# MI0283QT_v11.net
KiCad netlist of a schematic drawn in EAGLE
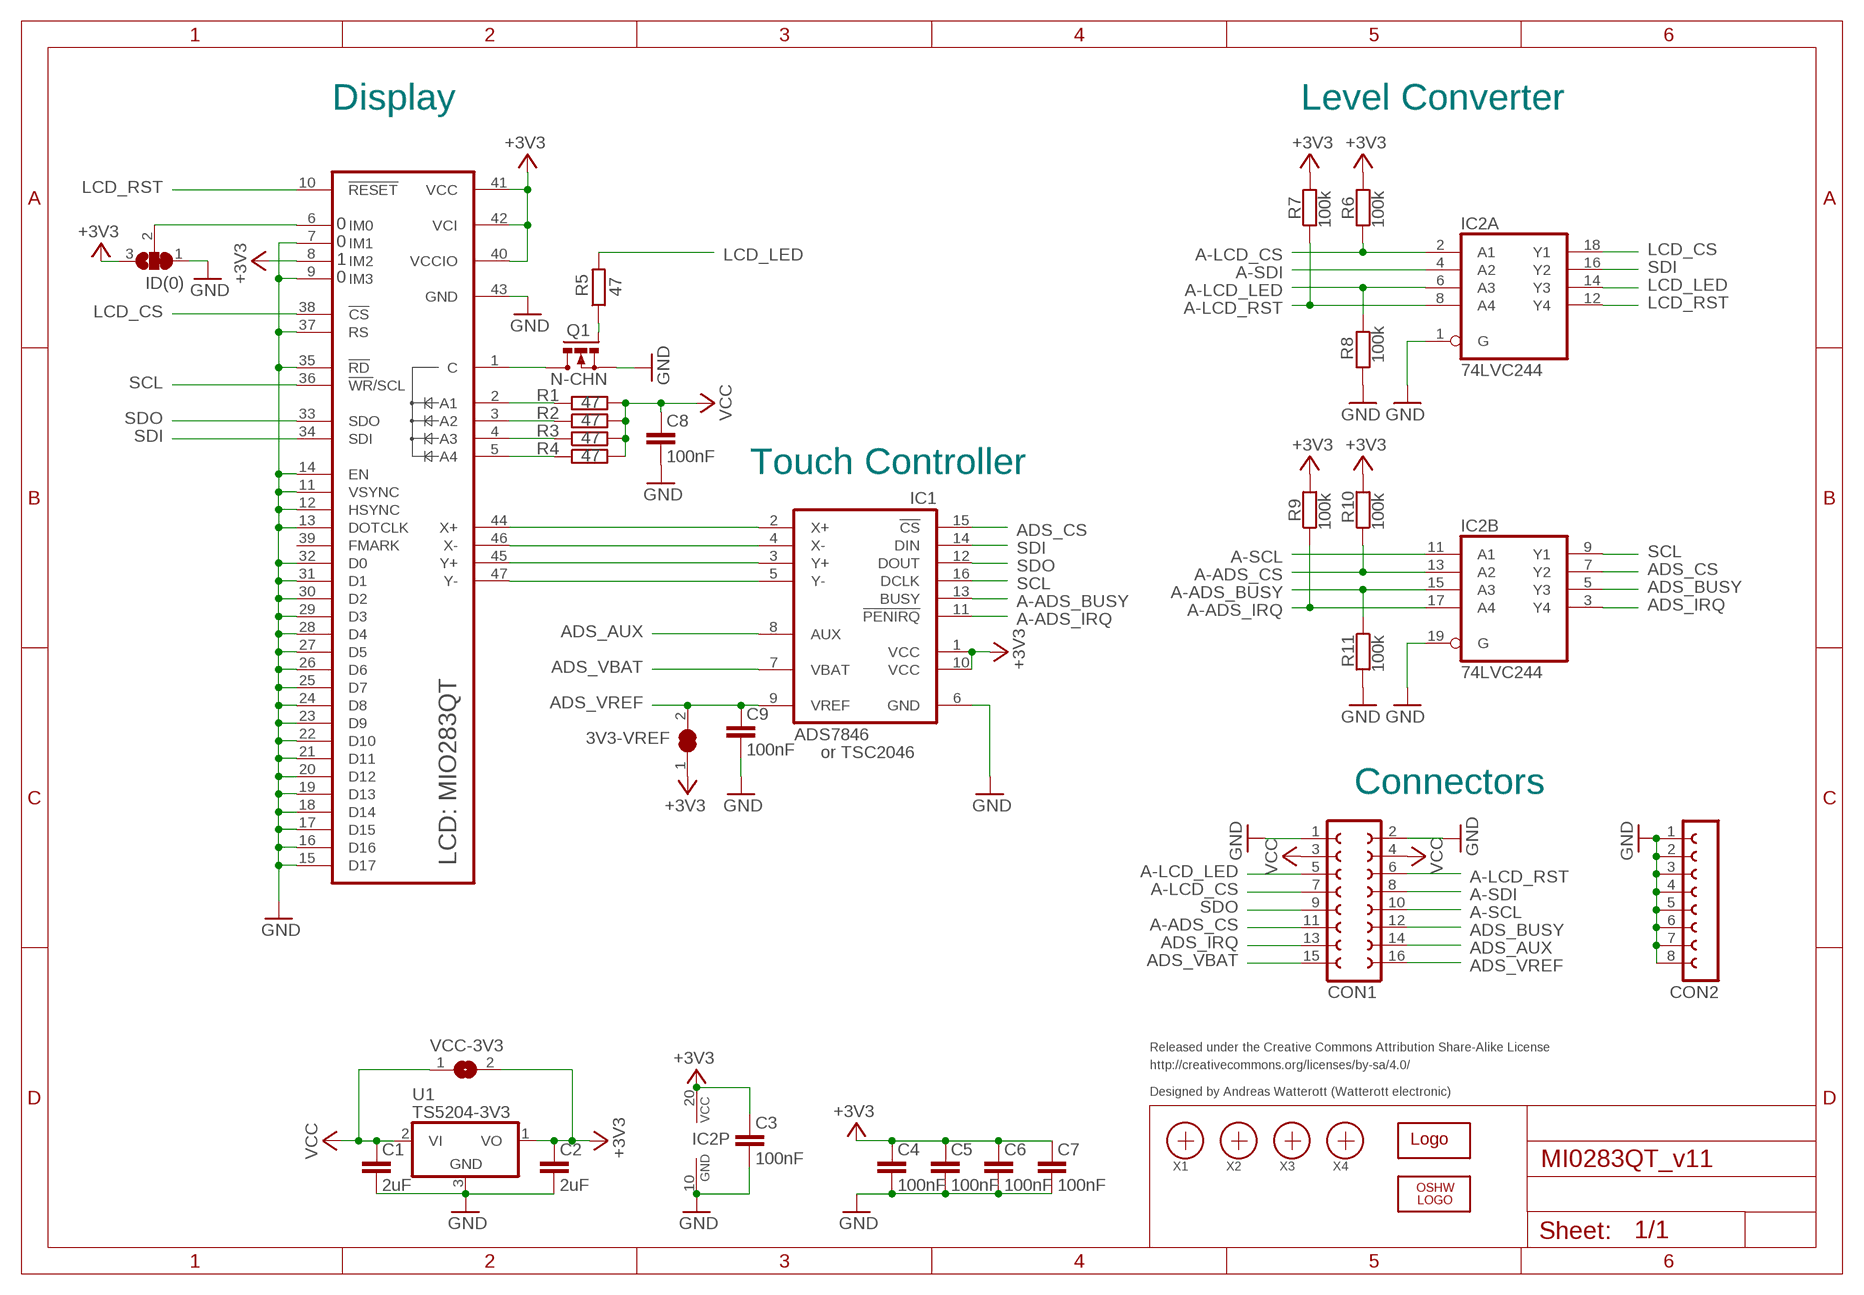
[diagram p0: schematic, sheet 1]

(export (version "E")
  (design (tool "Eeschema 10.0.6"))
  (components
    (comp (ref "3V3-VREF")
      (value "SJ")
      (footprint "eagle-import:SJ")
      (libsource (lib "eagle-import") (part "SJ"))
    )
    (comp (ref "C1")
      (value "2uF")
      (footprint "eagle-import:C0805")
      (libsource (lib "eagle-import") (part "C-EUC0805"))
    )
    (comp (ref "C2")
      (value "2uF")
      (footprint "eagle-import:C0805")
      (libsource (lib "eagle-import") (part "C-EUC0805"))
    )
    (comp (ref "C3")
      (value "100nF")
      (footprint "eagle-import:C0603")
      (libsource (lib "eagle-import") (part "C-EUC0603"))
    )
    (comp (ref "C4")
      (value "100nF")
      (footprint "eagle-import:C0603")
      (libsource (lib "eagle-import") (part "C-EUC0603"))
    )
    (comp (ref "C5")
      (value "100nF")
      (footprint "eagle-import:C0603")
      (libsource (lib "eagle-import") (part "C-EUC0603"))
    )
    (comp (ref "C6")
      (value "100nF")
      (footprint "eagle-import:C0603")
      (libsource (lib "eagle-import") (part "C-EUC0603"))
    )
    (comp (ref "C7")
      (value "100nF")
      (footprint "eagle-import:C0603")
      (libsource (lib "eagle-import") (part "C-EUC0603"))
    )
    (comp (ref "C8")
      (value "100nF")
      (footprint "eagle-import:C0603")
      (libsource (lib "eagle-import") (part "C-EUC0603"))
    )
    (comp (ref "C9")
      (value "100nF")
      (footprint "eagle-import:C0603")
      (libsource (lib "eagle-import") (part "C-EUC0603"))
    )
    (comp (ref "CON1")
      (value "FE08-2")
      (footprint "eagle-import:FE08-2")
      (libsource (lib "eagle-import") (part "FE08-2"))
    )
    (comp (ref "CON2")
      (value "FE08-1")
      (footprint "eagle-import:FE08")
      (libsource (lib "eagle-import") (part "FE08-1"))
    )
    (comp (ref "IC1")
      (value "ADS7846")
      (footprint "eagle-import:SSOP16")
      (libsource (lib "eagle-import") (part "ADS7846"))
    )
    (comp (ref "IC2")
      (value "74LVC244")
      (footprint "eagle-import:SO20W")
      (libsource (lib "eagle-import") (part "74244DWHC"))
    )
    (comp (ref "ID(0)")
      (value "SJ2W")
      (footprint "eagle-import:SJ_2")
      (libsource (lib "eagle-import") (part "SJ2W"))
    )
    (comp (ref "LCD")
      (value "MI0283QT")
      (footprint "eagle-import:MI0283QT")
      (libsource (lib "eagle-import") (part "MI0283QT"))
    )
    (comp (ref "LOGO1")
      (value "OSHW_LOGO_6MILX0150-NT")
      (footprint "eagle-import:OSHW_6X150_NOTEXT")
      (libsource (lib "eagle-import") (part "OSHW_LOGO_6MILX0150-NT"))
    )
    (comp (ref "Q1")
      (value "N-CHN")
      (footprint "eagle-import:MICRO3")
      (libsource (lib "eagle-import") (part "IRLML2502"))
    )
    (comp (ref "R1")
      (value "47")
      (footprint "eagle-import:R0603")
      (libsource (lib "eagle-import") (part "R-EU_R0603"))
    )
    (comp (ref "R2")
      (value "47")
      (footprint "eagle-import:R0603")
      (libsource (lib "eagle-import") (part "R-EU_R0603"))
    )
    (comp (ref "R3")
      (value "47")
      (footprint "eagle-import:R0603")
      (libsource (lib "eagle-import") (part "R-EU_R0603"))
    )
    (comp (ref "R4")
      (value "47")
      (footprint "eagle-import:R0603")
      (libsource (lib "eagle-import") (part "R-EU_R0603"))
    )
    (comp (ref "R5")
      (value "47")
      (footprint "eagle-import:R0603")
      (libsource (lib "eagle-import") (part "R-EU_R0603"))
    )
    (comp (ref "R6")
      (value "100k")
      (footprint "eagle-import:R0603")
      (libsource (lib "eagle-import") (part "R-EU_R0603"))
    )
    (comp (ref "R7")
      (value "100k")
      (footprint "eagle-import:R0603")
      (libsource (lib "eagle-import") (part "R-EU_R0603"))
    )
    (comp (ref "R8")
      (value "100k")
      (footprint "eagle-import:R0603")
      (libsource (lib "eagle-import") (part "R-EU_R0603"))
    )
    (comp (ref "R9")
      (value "100k")
      (footprint "eagle-import:R0603")
      (libsource (lib "eagle-import") (part "R-EU_R0603"))
    )
    (comp (ref "R10")
      (value "100k")
      (footprint "eagle-import:R0603")
      (libsource (lib "eagle-import") (part "R-EU_R0603"))
    )
    (comp (ref "R11")
      (value "100k")
      (footprint "eagle-import:R0603")
      (libsource (lib "eagle-import") (part "R-EU_R0603"))
    )
    (comp (ref "U$1")
      (value "WE-LOGO")
      (footprint "eagle-import:WE-LOGO")
      (libsource (lib "eagle-import") (part "WE-LOGO"))
    )
    (comp (ref "U1")
      (value "TS5204-3V3")
      (footprint "eagle-import:SOT23")
      (libsource (lib "eagle-import") (part "TS5204"))
    )
    (comp (ref "VCC-3V3")
      (value "SJ")
      (footprint "eagle-import:SJ")
      (libsource (lib "eagle-import") (part "SJ"))
    )
    (comp (ref "X1")
      (value "PASSER")
      (footprint "eagle-import:PASSER")
      (libsource (lib "eagle-import") (part "PASSER"))
    )
    (comp (ref "X2")
      (value "PASSER")
      (footprint "eagle-import:PASSER")
      (libsource (lib "eagle-import") (part "PASSER"))
    )
    (comp (ref "X3")
      (value "PASSER")
      (footprint "eagle-import:PASSER")
      (libsource (lib "eagle-import") (part "PASSER"))
    )
    (comp (ref "X4")
      (value "PASSER")
      (footprint "eagle-import:PASSER")
      (libsource (lib "eagle-import") (part "PASSER"))
    )
  )
  (nets
    (net (code "1") (name "+3V3") (class "Default")
      (node (ref "3V3-VREF") (pin "1") (pinfunction "1_1") (pintype "passive"))
      (node (ref "C2") (pin "1") (pinfunction "1_1") (pintype "passive"))
      (node (ref "C3") (pin "1") (pinfunction "1_1") (pintype "passive"))
      (node (ref "C4") (pin "1") (pinfunction "1_1") (pintype "passive"))
      (node (ref "C5") (pin "1") (pinfunction "1_1") (pintype "passive"))
      (node (ref "C6") (pin "1") (pinfunction "1_1") (pintype "passive"))
      (node (ref "C7") (pin "1") (pinfunction "1_1") (pintype "passive"))
      (node (ref "IC1") (pin "1") (pinfunction "VCC_1") (pintype "power_in"))
      (node (ref "IC1") (pin "10") (pinfunction "VCC_10") (pintype "power_in"))
      (node (ref "IC2") (pin "20") (pinfunction "VCC_20") (pintype "power_in"))
      (node (ref "ID(0)") (pin "3") (pinfunction "3_3") (pintype "passive"))
      (node (ref "LCD") (pin "40") (pinfunction "VCCIO_40") (pintype "power_in"))
      (node (ref "LCD") (pin "41") (pinfunction "VCC_41") (pintype "power_in"))
      (node (ref "LCD") (pin "42") (pinfunction "VCI_42") (pintype "power_in"))
      (node (ref "LCD") (pin "8") (pinfunction "IM2_8") (pintype "input"))
      (node (ref "R10") (pin "2") (pinfunction "2_2") (pintype "passive"))
      (node (ref "R6") (pin "2") (pinfunction "2_2") (pintype "passive"))
      (node (ref "R7") (pin "2") (pinfunction "2_2") (pintype "passive"))
      (node (ref "R9") (pin "2") (pinfunction "2_2") (pintype "passive"))
      (node (ref "U1") (pin "1") (pinfunction "VO_1") (pintype "passive"))
      (node (ref "VCC-3V3") (pin "2") (pinfunction "2_2") (pintype "passive"))
    )
    (net (code "2") (name "/A-ADS_BUSY") (class "Default")
      (node (ref "IC1") (pin "13") (pinfunction "BUSY_13") (pintype "output"))
      (node (ref "IC2") (pin "15") (pinfunction "A3_15") (pintype "input"))
      (node (ref "R11") (pin "1") (pinfunction "1_1") (pintype "passive"))
    )
    (net (code "3") (name "/A-ADS_CS") (class "Default")
      (node (ref "CON1") (pin "11") (pinfunction "11_11") (pintype "passive"))
      (node (ref "IC2") (pin "13") (pinfunction "A2_13") (pintype "input"))
      (node (ref "R10") (pin "1") (pinfunction "1_1") (pintype "passive"))
    )
    (net (code "4") (name "/A-ADS_IRQ") (class "Default")
      (node (ref "IC1") (pin "11") (pinfunction "~{PENIRQ}_11") (pintype "output"))
      (node (ref "IC2") (pin "17") (pinfunction "A4_17") (pintype "input"))
      (node (ref "R9") (pin "1") (pinfunction "1_1") (pintype "passive"))
    )
    (net (code "5") (name "/A-LCD_CS") (class "Default")
      (node (ref "CON1") (pin "7") (pinfunction "7_7") (pintype "passive"))
      (node (ref "IC2") (pin "2") (pinfunction "A1_2") (pintype "input"))
      (node (ref "R6") (pin "1") (pinfunction "1_1") (pintype "passive"))
    )
    (net (code "6") (name "/A-LCD_LED") (class "Default")
      (node (ref "CON1") (pin "5") (pinfunction "5_5") (pintype "passive"))
      (node (ref "IC2") (pin "6") (pinfunction "A3_6") (pintype "input"))
      (node (ref "R8") (pin "1") (pinfunction "1_1") (pintype "passive"))
    )
    (net (code "7") (name "/A-LCD_RST") (class "Default")
      (node (ref "CON1") (pin "6") (pinfunction "6_6") (pintype "passive"))
      (node (ref "IC2") (pin "8") (pinfunction "A4_8") (pintype "input"))
      (node (ref "R7") (pin "1") (pinfunction "1_1") (pintype "passive"))
    )
    (net (code "8") (name "/A-SCL") (class "Default")
      (node (ref "CON1") (pin "10") (pinfunction "10_10") (pintype "passive"))
      (node (ref "IC2") (pin "11") (pinfunction "A1_11") (pintype "input"))
    )
    (net (code "9") (name "/A-SDI") (class "Default")
      (node (ref "CON1") (pin "8") (pinfunction "8_8") (pintype "passive"))
      (node (ref "IC2") (pin "4") (pinfunction "A2_4") (pintype "input"))
    )
    (net (code "10") (name "/ADS_AUX") (class "Default")
      (node (ref "CON1") (pin "14") (pinfunction "14_14") (pintype "passive"))
      (node (ref "IC1") (pin "8") (pinfunction "AUX_8") (pintype "input"))
    )
    (net (code "11") (name "/ADS_BUSY") (class "Default")
      (node (ref "CON1") (pin "12") (pinfunction "12_12") (pintype "passive"))
      (node (ref "IC2") (pin "5") (pinfunction "Y3_5") (pintype "tri_state"))
    )
    (net (code "12") (name "/ADS_CS") (class "Default")
      (node (ref "IC1") (pin "15") (pinfunction "~{CS}_15") (pintype "input"))
      (node (ref "IC2") (pin "7") (pinfunction "Y2_7") (pintype "tri_state"))
    )
    (net (code "13") (name "/ADS_IRQ") (class "Default")
      (node (ref "CON1") (pin "13") (pinfunction "13_13") (pintype "passive"))
      (node (ref "IC2") (pin "3") (pinfunction "Y4_3") (pintype "tri_state"))
    )
    (net (code "14") (name "/ADS_VBAT") (class "Default")
      (node (ref "CON1") (pin "15") (pinfunction "15_15") (pintype "passive"))
      (node (ref "IC1") (pin "7") (pinfunction "VBAT_7") (pintype "input"))
    )
    (net (code "15") (name "/ADS_VREF") (class "Default")
      (node (ref "3V3-VREF") (pin "2") (pinfunction "2_2") (pintype "passive"))
      (node (ref "C9") (pin "1") (pinfunction "1_1") (pintype "passive"))
      (node (ref "CON1") (pin "16") (pinfunction "16_16") (pintype "passive"))
      (node (ref "IC1") (pin "9") (pinfunction "VREF_9") (pintype "bidirectional"))
    )
    (net (code "16") (name "/LCD_CS") (class "Default")
      (node (ref "IC2") (pin "18") (pinfunction "Y1_18") (pintype "tri_state"))
      (node (ref "LCD") (pin "38") (pinfunction "~{CS}_38") (pintype "input"))
    )
    (net (code "17") (name "/LCD_LED") (class "Default")
      (node (ref "IC2") (pin "14") (pinfunction "Y3_14") (pintype "tri_state"))
      (node (ref "R5") (pin "2") (pinfunction "2_2") (pintype "passive"))
    )
    (net (code "18") (name "/LCD_RST") (class "Default")
      (node (ref "IC2") (pin "12") (pinfunction "Y4_12") (pintype "tri_state"))
      (node (ref "LCD") (pin "10") (pinfunction "~{RESET}_10") (pintype "input"))
    )
    (net (code "19") (name "/SCL") (class "Default")
      (node (ref "IC1") (pin "16") (pinfunction "DCLK_16") (pintype "output"))
      (node (ref "IC2") (pin "9") (pinfunction "Y1_9") (pintype "tri_state"))
      (node (ref "LCD") (pin "36") (pinfunction "~{WR}/SCL_36") (pintype "input"))
    )
    (net (code "20") (name "/SDI") (class "Default")
      (node (ref "IC1") (pin "14") (pinfunction "DIN_14") (pintype "input"))
      (node (ref "IC2") (pin "16") (pinfunction "Y2_16") (pintype "tri_state"))
      (node (ref "LCD") (pin "34") (pinfunction "SDI_34") (pintype "input"))
    )
    (net (code "21") (name "/SDO") (class "Default")
      (node (ref "CON1") (pin "9") (pinfunction "9_9") (pintype "passive"))
      (node (ref "IC1") (pin "12") (pinfunction "DOUT_12") (pintype "input"))
      (node (ref "LCD") (pin "33") (pinfunction "SDO_33") (pintype "output"))
    )
    (net (code "22") (name "GND") (class "Default")
      (node (ref "C1") (pin "2") (pinfunction "2_2") (pintype "passive"))
      (node (ref "C2") (pin "2") (pinfunction "2_2") (pintype "passive"))
      (node (ref "C3") (pin "2") (pinfunction "2_2") (pintype "passive"))
      (node (ref "C4") (pin "2") (pinfunction "2_2") (pintype "passive"))
      (node (ref "C5") (pin "2") (pinfunction "2_2") (pintype "passive"))
      (node (ref "C6") (pin "2") (pinfunction "2_2") (pintype "passive"))
      (node (ref "C7") (pin "2") (pinfunction "2_2") (pintype "passive"))
      (node (ref "C8") (pin "2") (pinfunction "2_2") (pintype "passive"))
      (node (ref "C9") (pin "2") (pinfunction "2_2") (pintype "passive"))
      (node (ref "CON1") (pin "1") (pinfunction "1_1") (pintype "passive"))
      (node (ref "CON1") (pin "2") (pinfunction "2_2") (pintype "passive"))
      (node (ref "CON2") (pin "1") (pinfunction "1_1") (pintype "passive"))
      (node (ref "CON2") (pin "2") (pinfunction "2_2") (pintype "passive"))
      (node (ref "CON2") (pin "3") (pinfunction "3_3") (pintype "passive"))
      (node (ref "CON2") (pin "4") (pinfunction "4_4") (pintype "passive"))
      (node (ref "CON2") (pin "5") (pinfunction "5_5") (pintype "passive"))
      (node (ref "CON2") (pin "6") (pinfunction "6_6") (pintype "passive"))
      (node (ref "CON2") (pin "7") (pinfunction "7_7") (pintype "passive"))
      (node (ref "CON2") (pin "8") (pinfunction "8_8") (pintype "passive"))
      (node (ref "IC1") (pin "6") (pinfunction "GND_6") (pintype "power_in"))
      (node (ref "IC2") (pin "1") (pinfunction "G_1") (pintype "input"))
      (node (ref "IC2") (pin "10") (pinfunction "GND_10") (pintype "power_in"))
      (node (ref "IC2") (pin "19") (pinfunction "G_19") (pintype "input"))
      (node (ref "ID(0)") (pin "1") (pinfunction "1_1") (pintype "passive"))
      (node (ref "LCD") (pin "11") (pinfunction "VSYNC_11") (pintype "input"))
      (node (ref "LCD") (pin "12") (pinfunction "HSYNC_12") (pintype "input"))
      (node (ref "LCD") (pin "13") (pinfunction "DOTCLK_13") (pintype "input"))
      (node (ref "LCD") (pin "14") (pinfunction "EN_14") (pintype "input"))
      (node (ref "LCD") (pin "15") (pinfunction "D17_15") (pintype "input"))
      (node (ref "LCD") (pin "16") (pinfunction "D16_16") (pintype "input"))
      (node (ref "LCD") (pin "17") (pinfunction "D15_17") (pintype "input"))
      (node (ref "LCD") (pin "18") (pinfunction "D14_18") (pintype "input"))
      (node (ref "LCD") (pin "19") (pinfunction "D13_19") (pintype "input"))
      (node (ref "LCD") (pin "20") (pinfunction "D12_20") (pintype "input"))
      (node (ref "LCD") (pin "21") (pinfunction "D11_21") (pintype "input"))
      (node (ref "LCD") (pin "22") (pinfunction "D10_22") (pintype "input"))
      (node (ref "LCD") (pin "23") (pinfunction "D9_23") (pintype "input"))
      (node (ref "LCD") (pin "24") (pinfunction "D8_24") (pintype "input"))
      (node (ref "LCD") (pin "25") (pinfunction "D7_25") (pintype "input"))
      (node (ref "LCD") (pin "26") (pinfunction "D6_26") (pintype "input"))
      (node (ref "LCD") (pin "27") (pinfunction "D5_27") (pintype "input"))
      (node (ref "LCD") (pin "28") (pinfunction "D4_28") (pintype "input"))
      (node (ref "LCD") (pin "29") (pinfunction "D3_29") (pintype "input"))
      (node (ref "LCD") (pin "30") (pinfunction "D2_30") (pintype "input"))
      (node (ref "LCD") (pin "31") (pinfunction "D1_31") (pintype "input"))
      (node (ref "LCD") (pin "32") (pinfunction "D0_32") (pintype "input"))
      (node (ref "LCD") (pin "35") (pinfunction "~{RD}_35") (pintype "input"))
      (node (ref "LCD") (pin "37") (pinfunction "RS_37") (pintype "input"))
      (node (ref "LCD") (pin "43") (pinfunction "GND_43") (pintype "power_in"))
      (node (ref "LCD") (pin "7") (pinfunction "IM1_7") (pintype "input"))
      (node (ref "LCD") (pin "9") (pinfunction "IM3_9") (pintype "input"))
      (node (ref "Q1") (pin "2") (pinfunction "S_2") (pintype "passive"))
      (node (ref "R11") (pin "2") (pinfunction "2_2") (pintype "passive"))
      (node (ref "R8") (pin "2") (pinfunction "2_2") (pintype "passive"))
      (node (ref "U1") (pin "3") (pinfunction "GND_3") (pintype "passive"))
    )
    (net (code "23") (name "Net-(IC1-X+)") (class "Default")
      (node (ref "IC1") (pin "2") (pinfunction "X+_2") (pintype "input"))
      (node (ref "LCD") (pin "44") (pinfunction "X+_44") (pintype "passive"))
    )
    (net (code "24") (name "Net-(IC1-X-)") (class "Default")
      (node (ref "IC1") (pin "4") (pinfunction "X-_4") (pintype "input"))
      (node (ref "LCD") (pin "46") (pinfunction "X-_46") (pintype "passive"))
    )
    (net (code "25") (name "Net-(IC1-Y+)") (class "Default")
      (node (ref "IC1") (pin "3") (pinfunction "Y+_3") (pintype "input"))
      (node (ref "LCD") (pin "45") (pinfunction "Y+_45") (pintype "passive"))
    )
    (net (code "26") (name "Net-(IC1-Y-)") (class "Default")
      (node (ref "IC1") (pin "5") (pinfunction "Y-_5") (pintype "input"))
      (node (ref "LCD") (pin "47") (pinfunction "Y-_47") (pintype "passive"))
    )
    (net (code "27") (name "Net-(LCD-A1)") (class "Default")
      (node (ref "LCD") (pin "2") (pinfunction "A1_2") (pintype "power_in"))
      (node (ref "R1") (pin "1") (pinfunction "1_1") (pintype "passive"))
    )
    (net (code "28") (name "Net-(LCD-A2)") (class "Default")
      (node (ref "LCD") (pin "3") (pinfunction "A2_3") (pintype "power_in"))
      (node (ref "R2") (pin "1") (pinfunction "1_1") (pintype "passive"))
    )
    (net (code "29") (name "Net-(LCD-A3)") (class "Default")
      (node (ref "LCD") (pin "4") (pinfunction "A3_4") (pintype "power_in"))
      (node (ref "R3") (pin "1") (pinfunction "1_1") (pintype "passive"))
    )
    (net (code "30") (name "Net-(LCD-A4)") (class "Default")
      (node (ref "LCD") (pin "5") (pinfunction "A4_5") (pintype "power_in"))
      (node (ref "R4") (pin "1") (pinfunction "1_1") (pintype "passive"))
    )
    (net (code "31") (name "Net-(LCD-C)") (class "Default")
      (node (ref "LCD") (pin "1") (pinfunction "C_1") (pintype "power_in"))
      (node (ref "Q1") (pin "3") (pinfunction "D_3") (pintype "passive"))
    )
    (net (code "32") (name "Net-(LCD-IM0)") (class "Default")
      (node (ref "ID(0)") (pin "2") (pinfunction "2_2") (pintype "passive"))
      (node (ref "LCD") (pin "6") (pinfunction "IM0_6") (pintype "input"))
    )
    (net (code "33") (name "Net-(Q1-G)") (class "Default")
      (node (ref "Q1") (pin "1") (pinfunction "G_1") (pintype "passive"))
      (node (ref "R5") (pin "1") (pinfunction "1_1") (pintype "passive"))
    )
    (net (code "34") (name "VCC") (class "Default")
      (node (ref "C1") (pin "1") (pinfunction "1_1") (pintype "passive"))
      (node (ref "C8") (pin "1") (pinfunction "1_1") (pintype "passive"))
      (node (ref "CON1") (pin "3") (pinfunction "3_3") (pintype "passive"))
      (node (ref "CON1") (pin "4") (pinfunction "4_4") (pintype "passive"))
      (node (ref "R1") (pin "2") (pinfunction "2_2") (pintype "passive"))
      (node (ref "R2") (pin "2") (pinfunction "2_2") (pintype "passive"))
      (node (ref "R3") (pin "2") (pinfunction "2_2") (pintype "passive"))
      (node (ref "R4") (pin "2") (pinfunction "2_2") (pintype "passive"))
      (node (ref "U1") (pin "2") (pinfunction "VI_2") (pintype "input"))
      (node (ref "VCC-3V3") (pin "1") (pinfunction "1_1") (pintype "passive"))
    )
    (net (code "35") (name "unconnected-(LCD-FMARK-Pad39)") (class "Default")
      (node (ref "LCD") (pin "39") (pinfunction "FMARK_39") (pintype "output"))
    )
  )
)
